# ncp1402-breakout.net
KiCad netlist of a schematic drawn in EAGLE
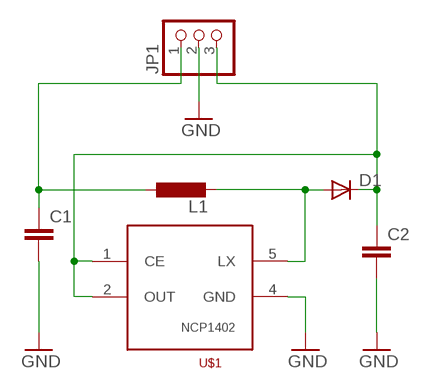
[diagram p0: schematic, sheet 1]

(export (version "E")
  (design (tool "Eeschema 10.0.6"))
  (components
    (comp (ref "C1")
      (value "C-EUC1210")
      (footprint "eagle-import:C1210")
      (libsource (lib "eagle-import") (part "C-EUC1210"))
    )
    (comp (ref "C2")
      (value "C-EUC1210")
      (footprint "eagle-import:C1210")
      (libsource (lib "eagle-import") (part "C-EUC1210"))
    )
    (comp (ref "D1")
      (value "DIODE-SOD80C")
      (footprint "eagle-import:SOD80C")
      (libsource (lib "eagle-import") (part "DIODE-SOD80C"))
    )
    (comp (ref "JP1")
      (value "PINHD-1X3")
      (footprint "eagle-import:1X03")
      (libsource (lib "eagle-import") (part "PINHD-1X3"))
    )
    (comp (ref "L1")
      (value "L-EUL1812")
      (footprint "eagle-import:L1812")
      (libsource (lib "eagle-import") (part "L-EUL1812"))
    )
    (comp (ref "U$1")
      (value "NCP1402-SOT23-5")
      (footprint "eagle-import:SOT23-5")
      (libsource (lib "eagle-import") (part "NCP1402-SOT23-5"))
    )
  )
  (nets
    (net (code "1") (name "GND") (class "Default")
      (node (ref "C1") (pin "2") (pinfunction "2_2") (pintype "passive"))
      (node (ref "C2") (pin "2") (pinfunction "2_2") (pintype "passive"))
      (node (ref "JP1") (pin "2") (pinfunction "2_2") (pintype "passive"))
      (node (ref "U$1") (pin "4") (pinfunction "GND_4") (pintype "bidirectional"))
    )
    (net (code "2") (name "Net-(C1-Pad1)") (class "Default")
      (node (ref "C1") (pin "1") (pinfunction "1_1") (pintype "passive"))
      (node (ref "JP1") (pin "1") (pinfunction "1_1") (pintype "passive"))
      (node (ref "L1") (pin "1") (pinfunction "1_1") (pintype "passive"))
    )
    (net (code "3") (name "Net-(U$1-CE)") (class "Default")
      (node (ref "C2") (pin "1") (pinfunction "1_1") (pintype "passive"))
      (node (ref "D1") (pin "C") (pinfunction "C_C") (pintype "passive"))
      (node (ref "JP1") (pin "3") (pinfunction "3_3") (pintype "passive"))
      (node (ref "U$1") (pin "1") (pinfunction "CE_1") (pintype "bidirectional"))
      (node (ref "U$1") (pin "2") (pinfunction "OUT_2") (pintype "bidirectional"))
    )
    (net (code "4") (name "Net-(U$1-LX)") (class "Default")
      (node (ref "D1") (pin "A") (pinfunction "A_A") (pintype "passive"))
      (node (ref "L1") (pin "2") (pinfunction "2_2") (pintype "passive"))
      (node (ref "U$1") (pin "5") (pinfunction "LX_5") (pintype "bidirectional"))
    )
  )
)
